# INA219x4_DoubleWing.net
KiCad netlist of a schematic drawn in EAGLE
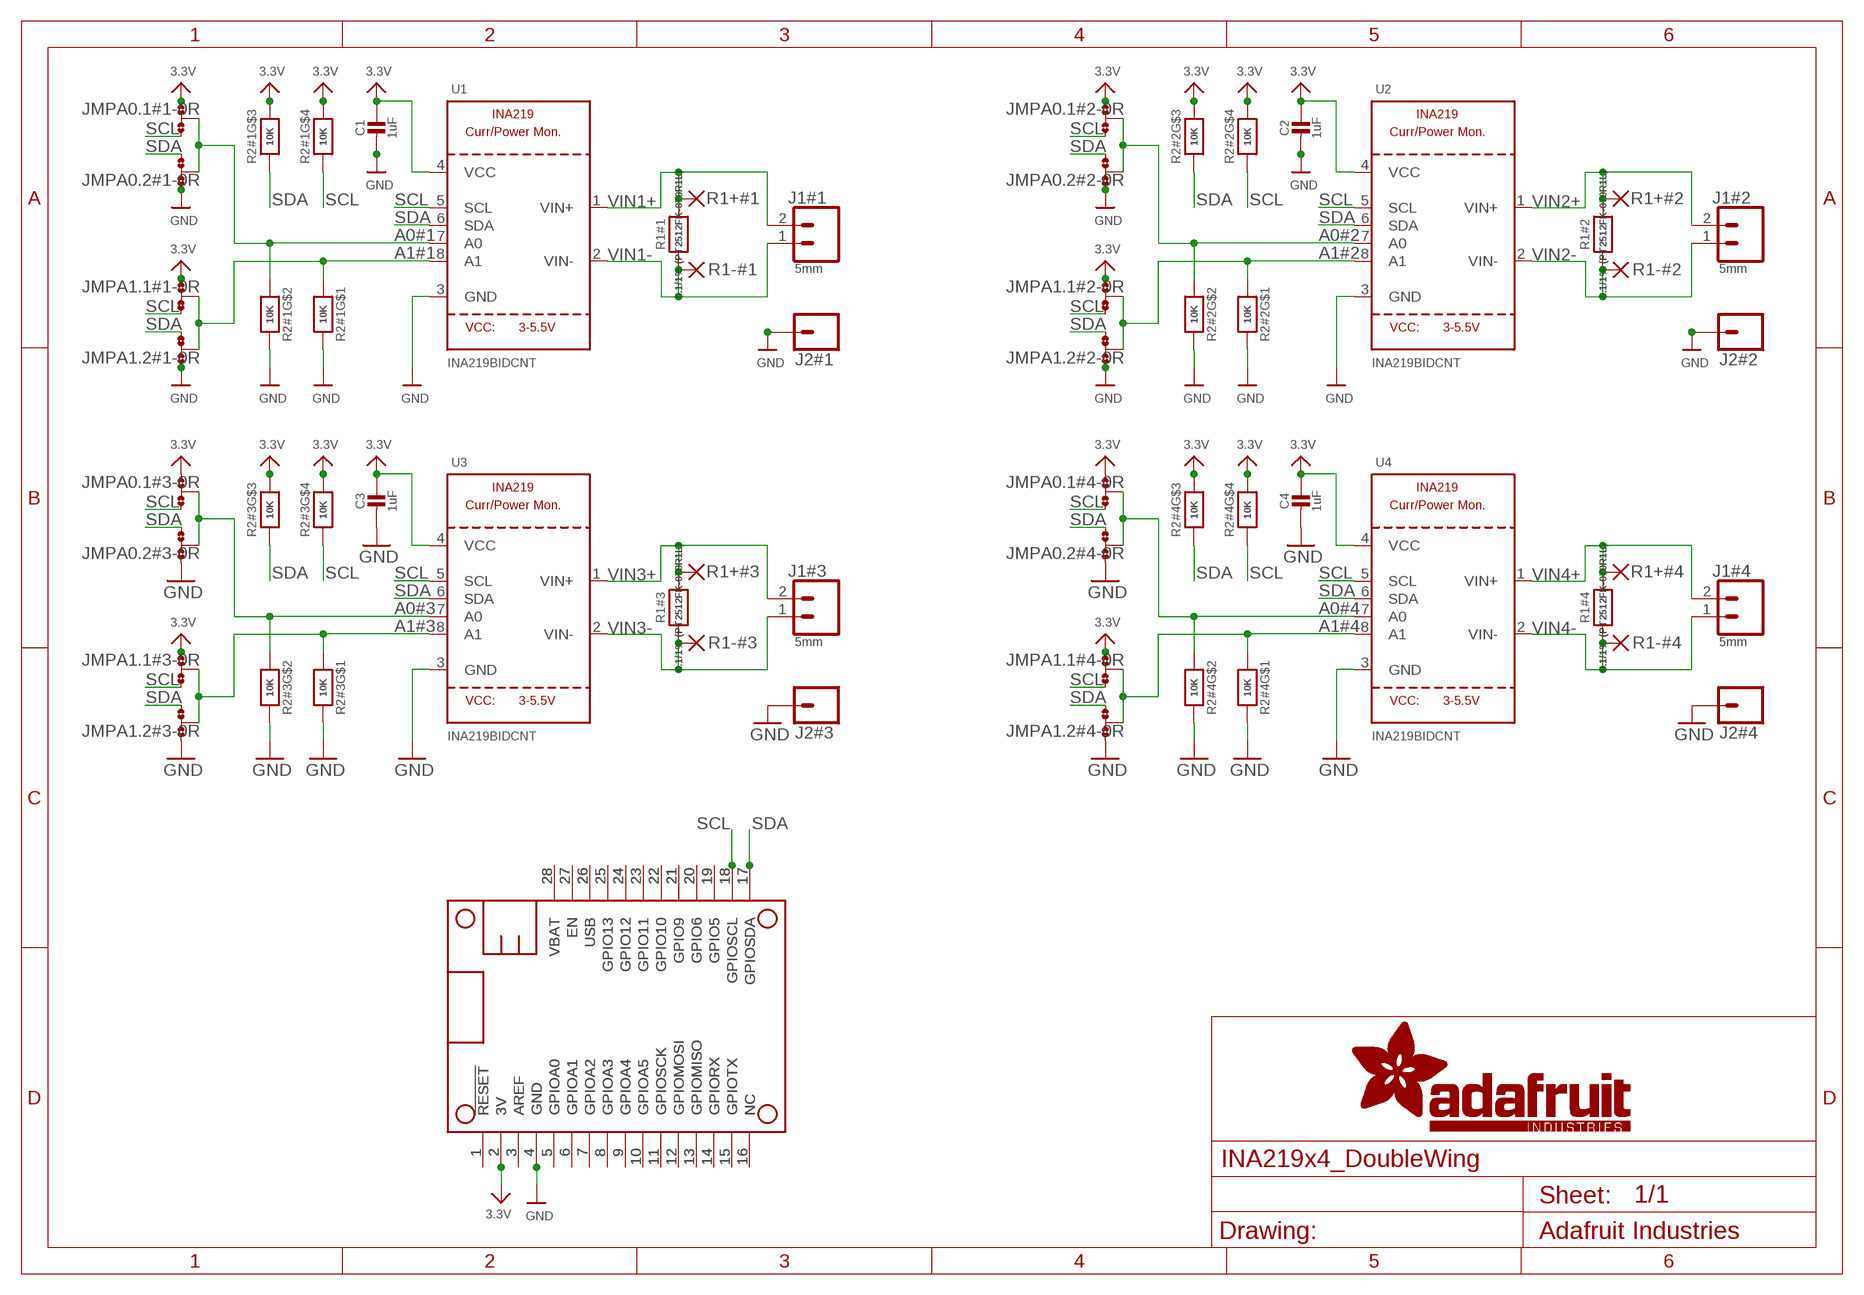
[diagram p0: schematic, sheet 1]

(export (version "E")
  (design (tool "Eeschema 10.0.6"))
  (components
    (comp (ref "C1")
      (value "1uF")
      (footprint "eagle-import:0805-NO@1")
      (libsource (lib "eagle-import") (part "CAP_CERAMIC0805-NOOUTLINE"))
    )
    (comp (ref "C2")
      (value "1uF")
      (footprint "eagle-import:0805-NO@1")
      (libsource (lib "eagle-import") (part "CAP_CERAMIC0805-NOOUTLINE"))
    )
    (comp (ref "C3")
      (value "1uF")
      (footprint "eagle-import:0805-NO@1")
      (libsource (lib "eagle-import") (part "CAP_CERAMIC0805-NOOUTLINE"))
    )
    (comp (ref "C4")
      (value "1uF")
      (footprint "eagle-import:0805-NO@1")
      (libsource (lib "eagle-import") (part "CAP_CERAMIC0805-NOOUTLINE"))
    )
    (comp (ref "J1#1")
      (value "5mm")
      (footprint "eagle-import:SCREWTERMINAL-5MM-2")
      (libsource (lib "eagle-import") (part "CONN_025MM"))
    )
    (comp (ref "J1#2")
      (value "5mm")
      (footprint "eagle-import:SCREWTERMINAL-5MM-2")
      (libsource (lib "eagle-import") (part "CONN_025MM"))
    )
    (comp (ref "J1#3")
      (value "5mm")
      (footprint "eagle-import:SCREWTERMINAL-5MM-2")
      (libsource (lib "eagle-import") (part "CONN_025MM"))
    )
    (comp (ref "J1#4")
      (value "5mm")
      (footprint "eagle-import:SCREWTERMINAL-5MM-2")
      (libsource (lib "eagle-import") (part "CONN_025MM"))
    )
    (comp (ref "J2#1")
      (value "CONN_01")
      (footprint "eagle-import:1X01")
      (libsource (lib "eagle-import") (part "CONN_01"))
    )
    (comp (ref "J2#2")
      (value "CONN_01")
      (footprint "eagle-import:1X01")
      (libsource (lib "eagle-import") (part "CONN_01"))
    )
    (comp (ref "J2#3")
      (value "CONN_01")
      (footprint "eagle-import:1X01")
      (libsource (lib "eagle-import") (part "CONN_01"))
    )
    (comp (ref "J2#4")
      (value "CONN_01")
      (footprint "eagle-import:1X01")
      (libsource (lib "eagle-import") (part "CONN_01"))
    )
    (comp (ref "JMPA0.1#1")
      (value "0R-JUMPD")
      (footprint "eagle-import:C0R-JMP_NONE")
      (libsource (lib "eagle-import") (part "0R-JUMPD"))
    )
    (comp (ref "JMPA0.1#2")
      (value "0R-JUMPD")
      (footprint "eagle-import:C0R-JMP_NONE")
      (libsource (lib "eagle-import") (part "0R-JUMPD"))
    )
    (comp (ref "JMPA0.1#3")
      (value "0R-JUMPD")
      (footprint "eagle-import:C0R-JMP_NONE")
      (libsource (lib "eagle-import") (part "0R-JUMPD"))
    )
    (comp (ref "JMPA0.1#4")
      (value "0R-JUMPD")
      (footprint "eagle-import:C0R-JMP_NONE")
      (libsource (lib "eagle-import") (part "0R-JUMPD"))
    )
    (comp (ref "JMPA0.2#1")
      (value "0R-JUMPD")
      (footprint "eagle-import:C0R-JMP_NONE")
      (libsource (lib "eagle-import") (part "0R-JUMPD"))
    )
    (comp (ref "JMPA0.2#2")
      (value "0R-JUMPD")
      (footprint "eagle-import:C0R-JMP_NONE")
      (libsource (lib "eagle-import") (part "0R-JUMPD"))
    )
    (comp (ref "JMPA0.2#3")
      (value "0R-JUMPD")
      (footprint "eagle-import:C0R-JMP_NONE")
      (libsource (lib "eagle-import") (part "0R-JUMPD"))
    )
    (comp (ref "JMPA0.2#4")
      (value "0R-JUMPD")
      (footprint "eagle-import:C0R-JMP_NONE")
      (libsource (lib "eagle-import") (part "0R-JUMPD"))
    )
    (comp (ref "JMPA1.1#1")
      (value "0R-JUMPD")
      (footprint "eagle-import:C0R-JMP_NONE")
      (libsource (lib "eagle-import") (part "0R-JUMPD"))
    )
    (comp (ref "JMPA1.1#2")
      (value "0R-JUMPD")
      (footprint "eagle-import:C0R-JMP_NONE")
      (libsource (lib "eagle-import") (part "0R-JUMPD"))
    )
    (comp (ref "JMPA1.1#3")
      (value "0R-JUMPD")
      (footprint "eagle-import:C0R-JMP_NONE")
      (libsource (lib "eagle-import") (part "0R-JUMPD"))
    )
    (comp (ref "JMPA1.1#4")
      (value "0R-JUMPD")
      (footprint "eagle-import:C0R-JMP_NONE")
      (libsource (lib "eagle-import") (part "0R-JUMPD"))
    )
    (comp (ref "JMPA1.2#1")
      (value "0R-JUMPD")
      (footprint "eagle-import:C0R-JMP_NONE")
      (libsource (lib "eagle-import") (part "0R-JUMPD"))
    )
    (comp (ref "JMPA1.2#2")
      (value "0R-JUMPD")
      (footprint "eagle-import:C0R-JMP_NONE")
      (libsource (lib "eagle-import") (part "0R-JUMPD"))
    )
    (comp (ref "JMPA1.2#3")
      (value "0R-JUMPD")
      (footprint "eagle-import:C0R-JMP_NONE")
      (libsource (lib "eagle-import") (part "0R-JUMPD"))
    )
    (comp (ref "JMPA1.2#4")
      (value "0R-JUMPD")
      (footprint "eagle-import:C0R-JMP_NONE")
      (libsource (lib "eagle-import") (part "0R-JUMPD"))
    )
    (comp (ref "MS1")
      (value "FEATHERWING_NODIM")
      (footprint "eagle-import:FEATHERWING_DIM")
      (libsource (lib "eagle-import") (part "FEATHERWING_NODIM"))
    )
    (comp (ref "MS2")
      (value "FEATHERWING_NODIM")
      (footprint "eagle-import:FEATHERWING_DIM")
      (libsource (lib "eagle-import") (part "FEATHERWING_NODIM"))
    )
    (comp (ref "R1#1")
      (value "0.1/1% (PT2512FK-070R1L)")
      (footprint "eagle-import:2512")
      (libsource (lib "eagle-import") (part "RESISTOR2512"))
    )
    (comp (ref "R1#2")
      (value "0.1/1% (PT2512FK-070R1L)")
      (footprint "eagle-import:2512")
      (libsource (lib "eagle-import") (part "RESISTOR2512"))
    )
    (comp (ref "R1#3")
      (value "0.1/1% (PT2512FK-070R1L)")
      (footprint "eagle-import:2512")
      (libsource (lib "eagle-import") (part "RESISTOR2512"))
    )
    (comp (ref "R1#4")
      (value "0.1/1% (PT2512FK-070R1L)")
      (footprint "eagle-import:2512")
      (libsource (lib "eagle-import") (part "RESISTOR2512"))
    )
    (comp (ref "R1+#1")
      (value "1,6/0,9")
      (footprint "eagle-import:1,6_0,9")
      (libsource (lib "eagle-import") (part "1,6/0,9"))
    )
    (comp (ref "R1+#2")
      (value "1,6/0,9")
      (footprint "eagle-import:1,6_0,9")
      (libsource (lib "eagle-import") (part "1,6/0,9"))
    )
    (comp (ref "R1+#3")
      (value "1,6/0,9")
      (footprint "eagle-import:1,6_0,9")
      (libsource (lib "eagle-import") (part "1,6/0,9"))
    )
    (comp (ref "R1+#4")
      (value "1,6/0,9")
      (footprint "eagle-import:1,6_0,9")
      (libsource (lib "eagle-import") (part "1,6/0,9"))
    )
    (comp (ref "R1-#1")
      (value "1,6/0,9")
      (footprint "eagle-import:1,6_0,9")
      (libsource (lib "eagle-import") (part "1,6/0,9"))
    )
    (comp (ref "R1-#2")
      (value "1,6/0,9")
      (footprint "eagle-import:1,6_0,9")
      (libsource (lib "eagle-import") (part "1,6/0,9"))
    )
    (comp (ref "R1-#3")
      (value "1,6/0,9")
      (footprint "eagle-import:1,6_0,9")
      (libsource (lib "eagle-import") (part "1,6/0,9"))
    )
    (comp (ref "R1-#4")
      (value "1,6/0,9")
      (footprint "eagle-import:1,6_0,9")
      (libsource (lib "eagle-import") (part "1,6/0,9"))
    )
    (comp (ref "R2#1")
      (value "10K")
      (footprint "eagle-import:RESPACK_4X0603")
      (libsource (lib "eagle-import") (part "RESISTOR_4PACK"))
    )
    (comp (ref "R2#2")
      (value "10K")
      (footprint "eagle-import:RESPACK_4X0603")
      (libsource (lib "eagle-import") (part "RESISTOR_4PACK"))
    )
    (comp (ref "R2#3")
      (value "10K")
      (footprint "eagle-import:RESPACK_4X0603")
      (libsource (lib "eagle-import") (part "RESISTOR_4PACK"))
    )
    (comp (ref "R2#4")
      (value "10K")
      (footprint "eagle-import:RESPACK_4X0603")
      (libsource (lib "eagle-import") (part "RESISTOR_4PACK"))
    )
    (comp (ref "U1")
      (value "INA219BIDCNT")
      (footprint "eagle-import:SOT23-8")
      (libsource (lib "eagle-import") (part "INA219"))
    )
    (comp (ref "U2")
      (value "INA219BIDCNT")
      (footprint "eagle-import:SOT23-8")
      (libsource (lib "eagle-import") (part "INA219"))
    )
    (comp (ref "U3")
      (value "INA219BIDCNT")
      (footprint "eagle-import:SOT23-8")
      (libsource (lib "eagle-import") (part "INA219"))
    )
    (comp (ref "U4")
      (value "INA219BIDCNT")
      (footprint "eagle-import:SOT23-8")
      (libsource (lib "eagle-import") (part "INA219"))
    )
  )
  (nets
    (net (code "1") (name "/A0#1") (class "Default")
      (node (ref "JMPA0.1#1") (pin "2") (pinfunction "2_2") (pintype "passive"))
      (node (ref "JMPA0.2#1") (pin "2") (pinfunction "2_2") (pintype "passive"))
      (node (ref "R2#1") (pin "2") (pinfunction "1_2") (pintype "passive"))
      (node (ref "U1") (pin "7") (pinfunction "A0_7") (pintype "bidirectional"))
    )
    (net (code "2") (name "/A0#2") (class "Default")
      (node (ref "JMPA0.1#2") (pin "2") (pinfunction "2_2") (pintype "passive"))
      (node (ref "JMPA0.2#2") (pin "2") (pinfunction "2_2") (pintype "passive"))
      (node (ref "R2#2") (pin "2") (pinfunction "1_2") (pintype "passive"))
      (node (ref "U2") (pin "7") (pinfunction "A0_7") (pintype "bidirectional"))
    )
    (net (code "3") (name "/A0#3") (class "Default")
      (node (ref "JMPA0.1#3") (pin "2") (pinfunction "2_2") (pintype "passive"))
      (node (ref "JMPA0.2#3") (pin "2") (pinfunction "2_2") (pintype "passive"))
      (node (ref "R2#3") (pin "2") (pinfunction "1_2") (pintype "passive"))
      (node (ref "U3") (pin "7") (pinfunction "A0_7") (pintype "bidirectional"))
    )
    (net (code "4") (name "/A0#4") (class "Default")
      (node (ref "JMPA0.1#4") (pin "2") (pinfunction "2_2") (pintype "passive"))
      (node (ref "JMPA0.2#4") (pin "2") (pinfunction "2_2") (pintype "passive"))
      (node (ref "R2#4") (pin "2") (pinfunction "1_2") (pintype "passive"))
      (node (ref "U4") (pin "7") (pinfunction "A0_7") (pintype "bidirectional"))
    )
    (net (code "5") (name "/A1#1") (class "Default")
      (node (ref "JMPA1.1#1") (pin "2") (pinfunction "2_2") (pintype "passive"))
      (node (ref "JMPA1.2#1") (pin "2") (pinfunction "2_2") (pintype "passive"))
      (node (ref "R2#1") (pin "1") (pinfunction "1_1") (pintype "passive"))
      (node (ref "U1") (pin "8") (pinfunction "A1_8") (pintype "bidirectional"))
    )
    (net (code "6") (name "/A1#2") (class "Default")
      (node (ref "JMPA1.1#2") (pin "2") (pinfunction "2_2") (pintype "passive"))
      (node (ref "JMPA1.2#2") (pin "2") (pinfunction "2_2") (pintype "passive"))
      (node (ref "R2#2") (pin "1") (pinfunction "1_1") (pintype "passive"))
      (node (ref "U2") (pin "8") (pinfunction "A1_8") (pintype "bidirectional"))
    )
    (net (code "7") (name "/A1#3") (class "Default")
      (node (ref "JMPA1.1#3") (pin "2") (pinfunction "2_2") (pintype "passive"))
      (node (ref "JMPA1.2#3") (pin "2") (pinfunction "2_2") (pintype "passive"))
      (node (ref "R2#3") (pin "1") (pinfunction "1_1") (pintype "passive"))
      (node (ref "U3") (pin "8") (pinfunction "A1_8") (pintype "bidirectional"))
    )
    (net (code "8") (name "/A1#4") (class "Default")
      (node (ref "JMPA1.1#4") (pin "2") (pinfunction "2_2") (pintype "passive"))
      (node (ref "JMPA1.2#4") (pin "2") (pinfunction "2_2") (pintype "passive"))
      (node (ref "R2#4") (pin "1") (pinfunction "1_1") (pintype "passive"))
      (node (ref "U4") (pin "8") (pinfunction "A1_8") (pintype "bidirectional"))
    )
    (net (code "9") (name "/SCL") (class "Default")
      (node (ref "JMPA0.1#1") (pin "3") (pinfunction "3_3") (pintype "passive"))
      (node (ref "JMPA0.1#2") (pin "3") (pinfunction "3_3") (pintype "passive"))
      (node (ref "JMPA0.1#3") (pin "3") (pinfunction "3_3") (pintype "passive"))
      (node (ref "JMPA0.1#4") (pin "3") (pinfunction "3_3") (pintype "passive"))
      (node (ref "JMPA1.1#1") (pin "3") (pinfunction "3_3") (pintype "passive"))
      (node (ref "JMPA1.1#2") (pin "3") (pinfunction "3_3") (pintype "passive"))
      (node (ref "JMPA1.1#3") (pin "3") (pinfunction "3_3") (pintype "passive"))
      (node (ref "JMPA1.1#4") (pin "3") (pinfunction "3_3") (pintype "passive"))
      (node (ref "MS1") (pin "18") (pinfunction "GPIOSCL_18") (pintype "bidirectional"))
      (node (ref "MS2") (pin "18") (pinfunction "GPIOSCL_18") (pintype "bidirectional"))
      (node (ref "R2#1") (pin "4") (pinfunction "1_4") (pintype "passive"))
      (node (ref "R2#2") (pin "4") (pinfunction "1_4") (pintype "passive"))
      (node (ref "R2#3") (pin "4") (pinfunction "1_4") (pintype "passive"))
      (node (ref "R2#4") (pin "4") (pinfunction "1_4") (pintype "passive"))
      (node (ref "U1") (pin "5") (pinfunction "SCL_5") (pintype "bidirectional"))
      (node (ref "U2") (pin "5") (pinfunction "SCL_5") (pintype "bidirectional"))
      (node (ref "U3") (pin "5") (pinfunction "SCL_5") (pintype "bidirectional"))
      (node (ref "U4") (pin "5") (pinfunction "SCL_5") (pintype "bidirectional"))
    )
    (net (code "10") (name "/SDA") (class "Default")
      (node (ref "JMPA0.2#1") (pin "1") (pinfunction "1_1") (pintype "passive"))
      (node (ref "JMPA0.2#2") (pin "1") (pinfunction "1_1") (pintype "passive"))
      (node (ref "JMPA0.2#3") (pin "1") (pinfunction "1_1") (pintype "passive"))
      (node (ref "JMPA0.2#4") (pin "1") (pinfunction "1_1") (pintype "passive"))
      (node (ref "JMPA1.2#1") (pin "1") (pinfunction "1_1") (pintype "passive"))
      (node (ref "JMPA1.2#2") (pin "1") (pinfunction "1_1") (pintype "passive"))
      (node (ref "JMPA1.2#3") (pin "1") (pinfunction "1_1") (pintype "passive"))
      (node (ref "JMPA1.2#4") (pin "1") (pinfunction "1_1") (pintype "passive"))
      (node (ref "MS1") (pin "17") (pinfunction "GPIOSDA_17") (pintype "bidirectional"))
      (node (ref "MS2") (pin "17") (pinfunction "GPIOSDA_17") (pintype "bidirectional"))
      (node (ref "R2#1") (pin "3") (pinfunction "1_3") (pintype "passive"))
      (node (ref "R2#2") (pin "3") (pinfunction "1_3") (pintype "passive"))
      (node (ref "R2#3") (pin "3") (pinfunction "1_3") (pintype "passive"))
      (node (ref "R2#4") (pin "3") (pinfunction "1_3") (pintype "passive"))
      (node (ref "U1") (pin "6") (pinfunction "SDA_6") (pintype "bidirectional"))
      (node (ref "U2") (pin "6") (pinfunction "SDA_6") (pintype "bidirectional"))
      (node (ref "U3") (pin "6") (pinfunction "SDA_6") (pintype "bidirectional"))
      (node (ref "U4") (pin "6") (pinfunction "SDA_6") (pintype "bidirectional"))
    )
    (net (code "11") (name "/VIN1+") (class "Default")
      (node (ref "J1#1") (pin "2") (pinfunction "2_2") (pintype "passive"))
      (node (ref "R1#1") (pin "2") (pinfunction "2_2") (pintype "passive"))
      (node (ref "R1+#1") (pin "1") (pinfunction "P_1") (pintype "passive"))
      (node (ref "U1") (pin "1") (pinfunction "VIN+_1") (pintype "bidirectional"))
    )
    (net (code "12") (name "/VIN1-") (class "Default")
      (node (ref "J1#1") (pin "1") (pinfunction "1_1") (pintype "passive"))
      (node (ref "R1#1") (pin "1") (pinfunction "1_1") (pintype "passive"))
      (node (ref "R1-#1") (pin "1") (pinfunction "P_1") (pintype "passive"))
      (node (ref "U1") (pin "2") (pinfunction "VIN-_2") (pintype "bidirectional"))
    )
    (net (code "13") (name "/VIN2+") (class "Default")
      (node (ref "J1#2") (pin "2") (pinfunction "2_2") (pintype "passive"))
      (node (ref "R1#2") (pin "2") (pinfunction "2_2") (pintype "passive"))
      (node (ref "R1+#2") (pin "1") (pinfunction "P_1") (pintype "passive"))
      (node (ref "U2") (pin "1") (pinfunction "VIN+_1") (pintype "bidirectional"))
    )
    (net (code "14") (name "/VIN2-") (class "Default")
      (node (ref "J1#2") (pin "1") (pinfunction "1_1") (pintype "passive"))
      (node (ref "R1#2") (pin "1") (pinfunction "1_1") (pintype "passive"))
      (node (ref "R1-#2") (pin "1") (pinfunction "P_1") (pintype "passive"))
      (node (ref "U2") (pin "2") (pinfunction "VIN-_2") (pintype "bidirectional"))
    )
    (net (code "15") (name "/VIN3+") (class "Default")
      (node (ref "J1#3") (pin "2") (pinfunction "2_2") (pintype "passive"))
      (node (ref "R1#3") (pin "2") (pinfunction "2_2") (pintype "passive"))
      (node (ref "R1+#3") (pin "1") (pinfunction "P_1") (pintype "passive"))
      (node (ref "U3") (pin "1") (pinfunction "VIN+_1") (pintype "bidirectional"))
    )
    (net (code "16") (name "/VIN3-") (class "Default")
      (node (ref "J1#3") (pin "1") (pinfunction "1_1") (pintype "passive"))
      (node (ref "R1#3") (pin "1") (pinfunction "1_1") (pintype "passive"))
      (node (ref "R1-#3") (pin "1") (pinfunction "P_1") (pintype "passive"))
      (node (ref "U3") (pin "2") (pinfunction "VIN-_2") (pintype "bidirectional"))
    )
    (net (code "17") (name "/VIN4+") (class "Default")
      (node (ref "J1#4") (pin "2") (pinfunction "2_2") (pintype "passive"))
      (node (ref "R1#4") (pin "2") (pinfunction "2_2") (pintype "passive"))
      (node (ref "R1+#4") (pin "1") (pinfunction "P_1") (pintype "passive"))
      (node (ref "U4") (pin "1") (pinfunction "VIN+_1") (pintype "bidirectional"))
    )
    (net (code "18") (name "/VIN4-") (class "Default")
      (node (ref "J1#4") (pin "1") (pinfunction "1_1") (pintype "passive"))
      (node (ref "R1#4") (pin "1") (pinfunction "1_1") (pintype "passive"))
      (node (ref "R1-#4") (pin "1") (pinfunction "P_1") (pintype "passive"))
      (node (ref "U4") (pin "2") (pinfunction "VIN-_2") (pintype "bidirectional"))
    )
    (net (code "19") (name "3.3V") (class "Default")
      (node (ref "C1") (pin "1") (pinfunction "1_1") (pintype "passive"))
      (node (ref "C2") (pin "1") (pinfunction "1_1") (pintype "passive"))
      (node (ref "C3") (pin "1") (pinfunction "1_1") (pintype "passive"))
      (node (ref "C4") (pin "1") (pinfunction "1_1") (pintype "passive"))
      (node (ref "JMPA0.1#1") (pin "1") (pinfunction "1_1") (pintype "passive"))
      (node (ref "JMPA0.1#2") (pin "1") (pinfunction "1_1") (pintype "passive"))
      (node (ref "JMPA0.1#3") (pin "1") (pinfunction "1_1") (pintype "passive"))
      (node (ref "JMPA0.1#4") (pin "1") (pinfunction "1_1") (pintype "passive"))
      (node (ref "JMPA1.1#1") (pin "1") (pinfunction "1_1") (pintype "passive"))
      (node (ref "JMPA1.1#2") (pin "1") (pinfunction "1_1") (pintype "passive"))
      (node (ref "JMPA1.1#3") (pin "1") (pinfunction "1_1") (pintype "passive"))
      (node (ref "JMPA1.1#4") (pin "1") (pinfunction "1_1") (pintype "passive"))
      (node (ref "MS1") (pin "2") (pinfunction "3V_2") (pintype "power_in"))
      (node (ref "MS2") (pin "2") (pinfunction "3V_2") (pintype "power_in"))
      (node (ref "R2#1") (pin "5") (pinfunction "2_5") (pintype "passive"))
      (node (ref "R2#1") (pin "6") (pinfunction "2_6") (pintype "passive"))
      (node (ref "R2#2") (pin "5") (pinfunction "2_5") (pintype "passive"))
      (node (ref "R2#2") (pin "6") (pinfunction "2_6") (pintype "passive"))
      (node (ref "R2#3") (pin "5") (pinfunction "2_5") (pintype "passive"))
      (node (ref "R2#3") (pin "6") (pinfunction "2_6") (pintype "passive"))
      (node (ref "R2#4") (pin "5") (pinfunction "2_5") (pintype "passive"))
      (node (ref "R2#4") (pin "6") (pinfunction "2_6") (pintype "passive"))
      (node (ref "U1") (pin "4") (pinfunction "VCC_4") (pintype "power_in"))
      (node (ref "U2") (pin "4") (pinfunction "VCC_4") (pintype "power_in"))
      (node (ref "U3") (pin "4") (pinfunction "VCC_4") (pintype "power_in"))
      (node (ref "U4") (pin "4") (pinfunction "VCC_4") (pintype "power_in"))
    )
    (net (code "20") (name "GND") (class "Default")
      (node (ref "C1") (pin "2") (pinfunction "2_2") (pintype "passive"))
      (node (ref "C2") (pin "2") (pinfunction "2_2") (pintype "passive"))
      (node (ref "C3") (pin "2") (pinfunction "2_2") (pintype "passive"))
      (node (ref "C4") (pin "2") (pinfunction "2_2") (pintype "passive"))
      (node (ref "J2#1") (pin "1") (pinfunction "1_1") (pintype "passive"))
      (node (ref "J2#2") (pin "1") (pinfunction "1_1") (pintype "passive"))
      (node (ref "J2#3") (pin "1") (pinfunction "1_1") (pintype "passive"))
      (node (ref "J2#4") (pin "1") (pinfunction "1_1") (pintype "passive"))
      (node (ref "JMPA0.2#1") (pin "3") (pinfunction "3_3") (pintype "passive"))
      (node (ref "JMPA0.2#2") (pin "3") (pinfunction "3_3") (pintype "passive"))
      (node (ref "JMPA0.2#3") (pin "3") (pinfunction "3_3") (pintype "passive"))
      (node (ref "JMPA0.2#4") (pin "3") (pinfunction "3_3") (pintype "passive"))
      (node (ref "JMPA1.2#1") (pin "3") (pinfunction "3_3") (pintype "passive"))
      (node (ref "JMPA1.2#2") (pin "3") (pinfunction "3_3") (pintype "passive"))
      (node (ref "JMPA1.2#3") (pin "3") (pinfunction "3_3") (pintype "passive"))
      (node (ref "JMPA1.2#4") (pin "3") (pinfunction "3_3") (pintype "passive"))
      (node (ref "MS1") (pin "4") (pinfunction "GND_4") (pintype "power_in"))
      (node (ref "MS2") (pin "4") (pinfunction "GND_4") (pintype "power_in"))
      (node (ref "R2#1") (pin "7") (pinfunction "2_7") (pintype "passive"))
      (node (ref "R2#1") (pin "8") (pinfunction "2_8") (pintype "passive"))
      (node (ref "R2#2") (pin "7") (pinfunction "2_7") (pintype "passive"))
      (node (ref "R2#2") (pin "8") (pinfunction "2_8") (pintype "passive"))
      (node (ref "R2#3") (pin "7") (pinfunction "2_7") (pintype "passive"))
      (node (ref "R2#3") (pin "8") (pinfunction "2_8") (pintype "passive"))
      (node (ref "R2#4") (pin "7") (pinfunction "2_7") (pintype "passive"))
      (node (ref "R2#4") (pin "8") (pinfunction "2_8") (pintype "passive"))
      (node (ref "U1") (pin "3") (pinfunction "GND_3") (pintype "power_in"))
      (node (ref "U2") (pin "3") (pinfunction "GND_3") (pintype "power_in"))
      (node (ref "U3") (pin "3") (pinfunction "GND_3") (pintype "power_in"))
      (node (ref "U4") (pin "3") (pinfunction "GND_3") (pintype "power_in"))
    )
    (net (code "21") (name "Net-(MS1-AREF)") (class "Default")
      (node (ref "MS1") (pin "3") (pinfunction "AREF_3") (pintype "passive"))
      (node (ref "MS2") (pin "3") (pinfunction "AREF_3") (pintype "passive"))
    )
    (net (code "22") (name "Net-(MS1-EN)") (class "Default")
      (node (ref "MS1") (pin "27") (pinfunction "EN_27") (pintype "passive"))
      (node (ref "MS2") (pin "27") (pinfunction "EN_27") (pintype "passive"))
    )
    (net (code "23") (name "Net-(MS1-GPIO5)") (class "Default")
      (node (ref "MS1") (pin "19") (pinfunction "GPIO5_19") (pintype "bidirectional"))
      (node (ref "MS2") (pin "19") (pinfunction "GPIO5_19") (pintype "bidirectional"))
    )
    (net (code "24") (name "Net-(MS1-GPIO6)") (class "Default")
      (node (ref "MS1") (pin "20") (pinfunction "GPIO6_20") (pintype "bidirectional"))
      (node (ref "MS2") (pin "20") (pinfunction "GPIO6_20") (pintype "bidirectional"))
    )
    (net (code "25") (name "Net-(MS1-GPIO9)") (class "Default")
      (node (ref "MS1") (pin "21") (pinfunction "GPIO9_21") (pintype "bidirectional"))
      (node (ref "MS2") (pin "21") (pinfunction "GPIO9_21") (pintype "bidirectional"))
    )
    (net (code "26") (name "Net-(MS1-GPIO10)") (class "Default")
      (node (ref "MS1") (pin "22") (pinfunction "GPIO10_22") (pintype "bidirectional"))
      (node (ref "MS2") (pin "22") (pinfunction "GPIO10_22") (pintype "bidirectional"))
    )
    (net (code "27") (name "Net-(MS1-GPIO11)") (class "Default")
      (node (ref "MS1") (pin "23") (pinfunction "GPIO11_23") (pintype "bidirectional"))
      (node (ref "MS2") (pin "23") (pinfunction "GPIO11_23") (pintype "bidirectional"))
    )
    (net (code "28") (name "Net-(MS1-GPIO12)") (class "Default")
      (node (ref "MS1") (pin "24") (pinfunction "GPIO12_24") (pintype "bidirectional"))
      (node (ref "MS2") (pin "24") (pinfunction "GPIO12_24") (pintype "bidirectional"))
    )
    (net (code "29") (name "Net-(MS1-GPIO13)") (class "Default")
      (node (ref "MS1") (pin "25") (pinfunction "GPIO13_25") (pintype "bidirectional"))
      (node (ref "MS2") (pin "25") (pinfunction "GPIO13_25") (pintype "bidirectional"))
    )
    (net (code "30") (name "Net-(MS1-GPIOA0)") (class "Default")
      (node (ref "MS1") (pin "5") (pinfunction "GPIOA0_5") (pintype "bidirectional"))
      (node (ref "MS2") (pin "5") (pinfunction "GPIOA0_5") (pintype "bidirectional"))
    )
    (net (code "31") (name "Net-(MS1-GPIOA1)") (class "Default")
      (node (ref "MS1") (pin "6") (pinfunction "GPIOA1_6") (pintype "bidirectional"))
      (node (ref "MS2") (pin "6") (pinfunction "GPIOA1_6") (pintype "bidirectional"))
    )
    (net (code "32") (name "Net-(MS1-GPIOA2)") (class "Default")
      (node (ref "MS1") (pin "7") (pinfunction "GPIOA2_7") (pintype "bidirectional"))
      (node (ref "MS2") (pin "7") (pinfunction "GPIOA2_7") (pintype "bidirectional"))
    )
    (net (code "33") (name "Net-(MS1-GPIOA3)") (class "Default")
      (node (ref "MS1") (pin "8") (pinfunction "GPIOA3_8") (pintype "bidirectional"))
      (node (ref "MS2") (pin "8") (pinfunction "GPIOA3_8") (pintype "bidirectional"))
    )
    (net (code "34") (name "Net-(MS1-GPIOA4)") (class "Default")
      (node (ref "MS1") (pin "9") (pinfunction "GPIOA4_9") (pintype "bidirectional"))
      (node (ref "MS2") (pin "9") (pinfunction "GPIOA4_9") (pintype "bidirectional"))
    )
    (net (code "35") (name "Net-(MS1-GPIOA5)") (class "Default")
      (node (ref "MS1") (pin "10") (pinfunction "GPIOA5_10") (pintype "bidirectional"))
      (node (ref "MS2") (pin "10") (pinfunction "GPIOA5_10") (pintype "bidirectional"))
    )
    (net (code "36") (name "Net-(MS1-GPIOMISO)") (class "Default")
      (node (ref "MS1") (pin "13") (pinfunction "GPIOMISO_13") (pintype "bidirectional"))
      (node (ref "MS2") (pin "13") (pinfunction "GPIOMISO_13") (pintype "bidirectional"))
    )
    (net (code "37") (name "Net-(MS1-GPIOMOSI)") (class "Default")
      (node (ref "MS1") (pin "12") (pinfunction "GPIOMOSI_12") (pintype "bidirectional"))
      (node (ref "MS2") (pin "12") (pinfunction "GPIOMOSI_12") (pintype "bidirectional"))
    )
    (net (code "38") (name "Net-(MS1-GPIORX)") (class "Default")
      (node (ref "MS1") (pin "14") (pinfunction "GPIORX_14") (pintype "bidirectional"))
      (node (ref "MS2") (pin "14") (pinfunction "GPIORX_14") (pintype "bidirectional"))
    )
    (net (code "39") (name "Net-(MS1-GPIOSCK)") (class "Default")
      (node (ref "MS1") (pin "11") (pinfunction "GPIOSCK_11") (pintype "bidirectional"))
      (node (ref "MS2") (pin "11") (pinfunction "GPIOSCK_11") (pintype "bidirectional"))
    )
    (net (code "40") (name "Net-(MS1-GPIOTX)") (class "Default")
      (node (ref "MS1") (pin "15") (pinfunction "GPIOTX_15") (pintype "bidirectional"))
      (node (ref "MS2") (pin "15") (pinfunction "GPIOTX_15") (pintype "bidirectional"))
    )
    (net (code "41") (name "Net-(MS1-NC)") (class "Default")
      (node (ref "MS1") (pin "16") (pinfunction "NC_16") (pintype "passive"))
      (node (ref "MS2") (pin "16") (pinfunction "NC_16") (pintype "passive"))
    )
    (net (code "42") (name "Net-(MS1-USB)") (class "Default")
      (node (ref "MS1") (pin "26") (pinfunction "USB_26") (pintype "power_in"))
      (node (ref "MS2") (pin "26") (pinfunction "USB_26") (pintype "power_in"))
    )
    (net (code "43") (name "Net-(MS1-VBAT)") (class "Default")
      (node (ref "MS1") (pin "28") (pinfunction "VBAT_28") (pintype "power_in"))
      (node (ref "MS2") (pin "28") (pinfunction "VBAT_28") (pintype "power_in"))
    )
    (net (code "44") (name "Net-(MS1-~{RESET})") (class "Default")
      (node (ref "MS1") (pin "1") (pinfunction "~{RESET}_1") (pintype "input"))
      (node (ref "MS2") (pin "1") (pinfunction "~{RESET}_1") (pintype "input"))
    )
  )
)
